# Power.net
KiCad netlist of a schematic drawn in Altium Designer
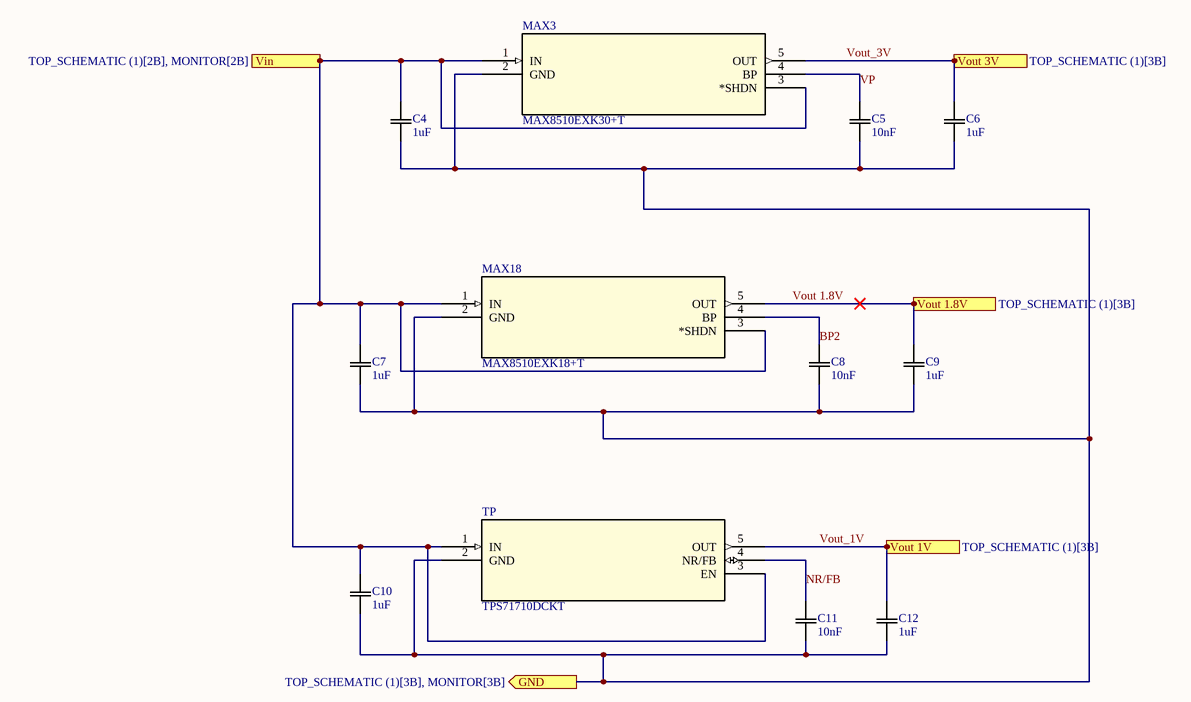
[diagram p0: Power.SchDoc]

(export (version "E")
  (design (tool "Eeschema 10.0.6"))
  (components
    (comp (ref "C4")
      (value "1uF")
      (footprint "CAP_CL10_SAM")
      (description "No Description Available")
      (fields
        (field (name "MANUFACTURER_PART_NUMBER") "CL10C120JB8NNNC")
        (field (name "COPYRIGHT") "Copyright (C) 2026 Ultra Librarian. All rights reserved.")
      )
      (libsource (lib "Cap_0603") (part "CL10C120JB8NNNC"))
    )
    (comp (ref "C5")
      (value "10nF")
      (footprint "CAP_CL10_SAM")
      (description "No Description Available")
      (fields
        (field (name "MANUFACTURER_PART_NUMBER") "CL10C120JB8NNNC")
        (field (name "COPYRIGHT") "Copyright (C) 2026 Ultra Librarian. All rights reserved.")
      )
      (libsource (lib "Cap_0603") (part "CL10C120JB8NNNC"))
    )
    (comp (ref "C6")
      (value "1uF")
      (footprint "CAP_CL10_SAM")
      (description "No Description Available")
      (fields
        (field (name "MANUFACTURER_PART_NUMBER") "CL10C120JB8NNNC")
        (field (name "COPYRIGHT") "Copyright (C) 2026 Ultra Librarian. All rights reserved.")
      )
      (libsource (lib "Cap_0603") (part "CL10C120JB8NNNC"))
    )
    (comp (ref "C7")
      (value "1uF")
      (footprint "CAP_CL10_SAM")
      (description "No Description Available")
      (fields
        (field (name "MANUFACTURER_PART_NUMBER") "CL10C120JB8NNNC")
        (field (name "COPYRIGHT") "Copyright (C) 2026 Ultra Librarian. All rights reserved.")
      )
      (libsource (lib "Cap_0603") (part "CL10C120JB8NNNC"))
    )
    (comp (ref "C8")
      (value "10nF")
      (footprint "CAP_CL10_SAM")
      (description "No Description Available")
      (fields
        (field (name "MANUFACTURER_PART_NUMBER") "CL10C120JB8NNNC")
        (field (name "COPYRIGHT") "Copyright (C) 2026 Ultra Librarian. All rights reserved.")
      )
      (libsource (lib "Cap_0603") (part "CL10C120JB8NNNC"))
    )
    (comp (ref "C9")
      (value "1uF")
      (footprint "CAP_CL10_SAM")
      (description "No Description Available")
      (fields
        (field (name "MANUFACTURER_PART_NUMBER") "CL10C120JB8NNNC")
        (field (name "COPYRIGHT") "Copyright (C) 2026 Ultra Librarian. All rights reserved.")
      )
      (libsource (lib "Cap_0603") (part "CL10C120JB8NNNC"))
    )
    (comp (ref "C10")
      (value "1uF")
      (footprint "CAP_CL10_SAM")
      (description "No Description Available")
      (fields
        (field (name "MANUFACTURER_PART_NUMBER") "CL10C120JB8NNNC")
        (field (name "COPYRIGHT") "Copyright (C) 2026 Ultra Librarian. All rights reserved.")
      )
      (libsource (lib "Cap_0603") (part "CL10C120JB8NNNC"))
    )
    (comp (ref "C11")
      (value "10nF")
      (footprint "CAP_CL10_SAM")
      (description "No Description Available")
      (fields
        (field (name "MANUFACTURER_PART_NUMBER") "CL10C120JB8NNNC")
        (field (name "COPYRIGHT") "Copyright (C) 2026 Ultra Librarian. All rights reserved.")
      )
      (libsource (lib "Cap_0603") (part "CL10C120JB8NNNC"))
    )
    (comp (ref "C12")
      (value "1uF")
      (footprint "CAP_CL10_SAM")
      (description "No Description Available")
      (fields
        (field (name "MANUFACTURER_PART_NUMBER") "CL10C120JB8NNNC")
        (field (name "COPYRIGHT") "Copyright (C) 2026 Ultra Librarian. All rights reserved.")
      )
      (libsource (lib "Cap_0603") (part "CL10C120JB8NNNC"))
    )
    (comp (ref "MAX3")
      (value "MAX8510EXK30+T")
      (footprint "21-0076E_MXM")
      (description "Ultra-Low-Noise, High PSRR, Low-Dropout, 120mA Linear Regulators")
      (fields (field (name "COPYRIGHT") "Copyright (C) 2026 Ultra Librarian. All rights reserved."))
      (libsource (lib "MAX8510EXK30&plus_T") (part "MAX8510EXK30+T"))
    )
    (comp (ref "MAX18")
      (value "MAX8510EXK18+T")
      (footprint "21-0076E_MXM")
      (description "Ultra-Low-Noise, High PSRR, Low-Dropout, 120mA Linear Regulators")
      (fields
        (field (name "MANUFACTURER_PART_NUMBER") "MAX8510EXK30+T")
        (field (name "COPYRIGHT") "Copyright (C) 2026 Ultra Librarian. All rights reserved.")
      )
      (libsource (lib "MAX8510EXK30&plus_T") (part "MAX8510EXK30+T"))
    )
    (comp (ref "TP")
      (value "TPS71710DCKT")
      (footprint "DCK5")
      (description "150-mA, high-PSRR, low-IQ, low-dropout voltage regulator with enable 5-SC70 -40 to 125")
      (fields (field (name "COPYRIGHT") "Copyright (C) 2026 Ultra Librarian. All rights reserved."))
      (libsource (lib "TPS71710DCKT") (part "TPS71710DCKT"))
    )
  )
  (nets
    (net (code "1") (name "/BP2") (class "Default")
      (node (ref "C8") (pin "2") (pinfunction "2_2") (pintype "passive"))
      (node (ref "MAX18") (pin "4") (pinfunction "BP_4") (pintype "passive"))
    )
    (net (code "2") (name "/GND") (class "Default")
      (node (ref "C10") (pin "1") (pinfunction "1_1") (pintype "passive"))
      (node (ref "C11") (pin "1") (pinfunction "1_1") (pintype "passive"))
      (node (ref "C12") (pin "1") (pinfunction "1_1") (pintype "passive"))
      (node (ref "C4") (pin "1") (pinfunction "1_1") (pintype "passive"))
      (node (ref "C5") (pin "1") (pinfunction "1_1") (pintype "passive"))
      (node (ref "C6") (pin "1") (pinfunction "1_1") (pintype "passive"))
      (node (ref "C7") (pin "1") (pinfunction "1_1") (pintype "passive"))
      (node (ref "C8") (pin "1") (pinfunction "1_1") (pintype "passive"))
      (node (ref "C9") (pin "1") (pinfunction "1_1") (pintype "passive"))
      (node (ref "MAX18") (pin "2") (pinfunction "GND_2") (pintype "power_in"))
      (node (ref "MAX3") (pin "2") (pinfunction "GND_2") (pintype "power_in"))
      (node (ref "TP") (pin "2") (pinfunction "GND_2") (pintype "power_in"))
    )
    (net (code "3") (name "/NR{slash}FB") (class "Default")
      (node (ref "C11") (pin "2") (pinfunction "2_2") (pintype "passive"))
      (node (ref "TP") (pin "4") (pinfunction "NR/FB_4") (pintype "bidirectional"))
    )
    (net (code "4") (name "/VP") (class "Default")
      (node (ref "C5") (pin "2") (pinfunction "2_2") (pintype "passive"))
      (node (ref "MAX3") (pin "4") (pinfunction "BP_4") (pintype "passive"))
    )
    (net (code "5") (name "/Vin") (class "Default")
      (node (ref "C10") (pin "2") (pinfunction "2_2") (pintype "passive"))
      (node (ref "C4") (pin "2") (pinfunction "2_2") (pintype "passive"))
      (node (ref "C7") (pin "2") (pinfunction "2_2") (pintype "passive"))
      (node (ref "MAX18") (pin "1") (pinfunction "IN_1") (pintype "input"))
      (node (ref "MAX18") (pin "3") (pinfunction "*SHDN_3") (pintype "passive"))
      (node (ref "MAX3") (pin "1") (pinfunction "IN_1") (pintype "input"))
      (node (ref "MAX3") (pin "3") (pinfunction "*SHDN_3") (pintype "passive"))
      (node (ref "TP") (pin "1") (pinfunction "IN_1") (pintype "input"))
      (node (ref "TP") (pin "3") (pinfunction "EN_3") (pintype "passive"))
    )
    (net (code "6") (name "/Vout 1.8V") (class "Default")
      (node (ref "C9") (pin "2") (pinfunction "2_2") (pintype "passive"))
      (node (ref "MAX18") (pin "5") (pinfunction "OUT_5") (pintype "output"))
    )
    (net (code "7") (name "/Vout_1V") (class "Default")
      (node (ref "C12") (pin "2") (pinfunction "2_2") (pintype "passive"))
      (node (ref "TP") (pin "5") (pinfunction "OUT_5") (pintype "output"))
    )
    (net (code "8") (name "/Vout_3V") (class "Default")
      (node (ref "C6") (pin "2") (pinfunction "2_2") (pintype "passive"))
      (node (ref "MAX3") (pin "5") (pinfunction "OUT_5") (pintype "output"))
    )
  )
)
